# LM555.net
KiCad netlist of a schematic drawn in EAGLE
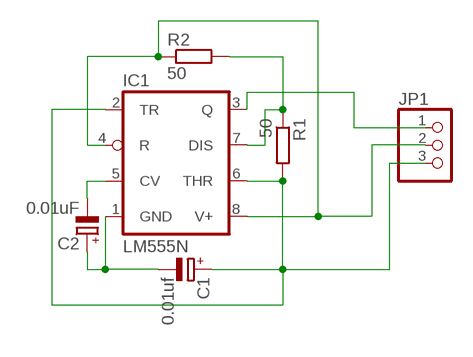
[diagram p0: schematic, sheet 1]

(export (version "E")
  (design (tool "Eeschema 10.0.6"))
  (components
    (comp (ref "C1")
      (value "0.01uf")
      (footprint "eagle-import:E2,5-6")
      (libsource (lib "eagle-import") (part "CPOL-EUE2.5-6"))
    )
    (comp (ref "C2")
      (value "0.01uF")
      (footprint "eagle-import:E2,5-6")
      (libsource (lib "eagle-import") (part "CPOL-EUE2.5-6"))
    )
    (comp (ref "IC1")
      (value "LM555N")
      (footprint "eagle-import:DIL08")
      (libsource (lib "eagle-import") (part "555NLM"))
    )
    (comp (ref "JP1")
      (value "PINHD-1X3")
      (footprint "eagle-import:1X03")
      (libsource (lib "eagle-import") (part "PINHD-1X3"))
    )
    (comp (ref "R1")
      (value "50")
      (footprint "eagle-import:0207_10")
      (libsource (lib "eagle-import") (part "R-EU_0207/10"))
    )
    (comp (ref "R2")
      (value "50")
      (footprint "eagle-import:0207_10")
      (libsource (lib "eagle-import") (part "R-EU_0207/10"))
    )
  )
  (nets
    (net (code "1") (name "Net-(IC1-CV)") (class "Default")
      (node (ref "C2") (pin "-") (pinfunction "-_-") (pintype "passive"))
      (node (ref "IC1") (pin "5") (pinfunction "CV_5") (pintype "input"))
    )
    (net (code "2") (name "Net-(IC1-DIS)") (class "Default")
      (node (ref "IC1") (pin "7") (pinfunction "DIS_7") (pintype "input"))
      (node (ref "R1") (pin "1") (pinfunction "1_1") (pintype "passive"))
      (node (ref "R2") (pin "2") (pinfunction "2_2") (pintype "passive"))
    )
    (net (code "3") (name "Net-(IC1-GND)") (class "Default")
      (node (ref "C1") (pin "-") (pinfunction "-_-") (pintype "passive"))
      (node (ref "C2") (pin "+") (pinfunction "+_+") (pintype "passive"))
      (node (ref "IC1") (pin "1") (pinfunction "GND_1") (pintype "power_in"))
    )
    (net (code "4") (name "Net-(IC1-Q)") (class "Default")
      (node (ref "IC1") (pin "3") (pinfunction "Q_3") (pintype "output"))
      (node (ref "JP1") (pin "1") (pinfunction "1_1") (pintype "passive"))
    )
    (net (code "5") (name "Net-(IC1-R)") (class "Default")
      (node (ref "IC1") (pin "4") (pinfunction "R_4") (pintype "input"))
      (node (ref "IC1") (pin "8") (pinfunction "V+_8") (pintype "power_in"))
      (node (ref "JP1") (pin "2") (pinfunction "2_2") (pintype "passive"))
      (node (ref "R2") (pin "1") (pinfunction "1_1") (pintype "passive"))
    )
    (net (code "6") (name "Net-(IC1-THR)") (class "Default")
      (node (ref "C1") (pin "+") (pinfunction "+_+") (pintype "passive"))
      (node (ref "IC1") (pin "2") (pinfunction "TR_2") (pintype "input"))
      (node (ref "IC1") (pin "6") (pinfunction "THR_6") (pintype "input"))
      (node (ref "JP1") (pin "3") (pinfunction "3_3") (pintype "passive"))
      (node (ref "R1") (pin "2") (pinfunction "2_2") (pintype "passive"))
    )
  )
)
